# usb_to_can.net
KiCad netlist of a schematic drawn in EAGLE
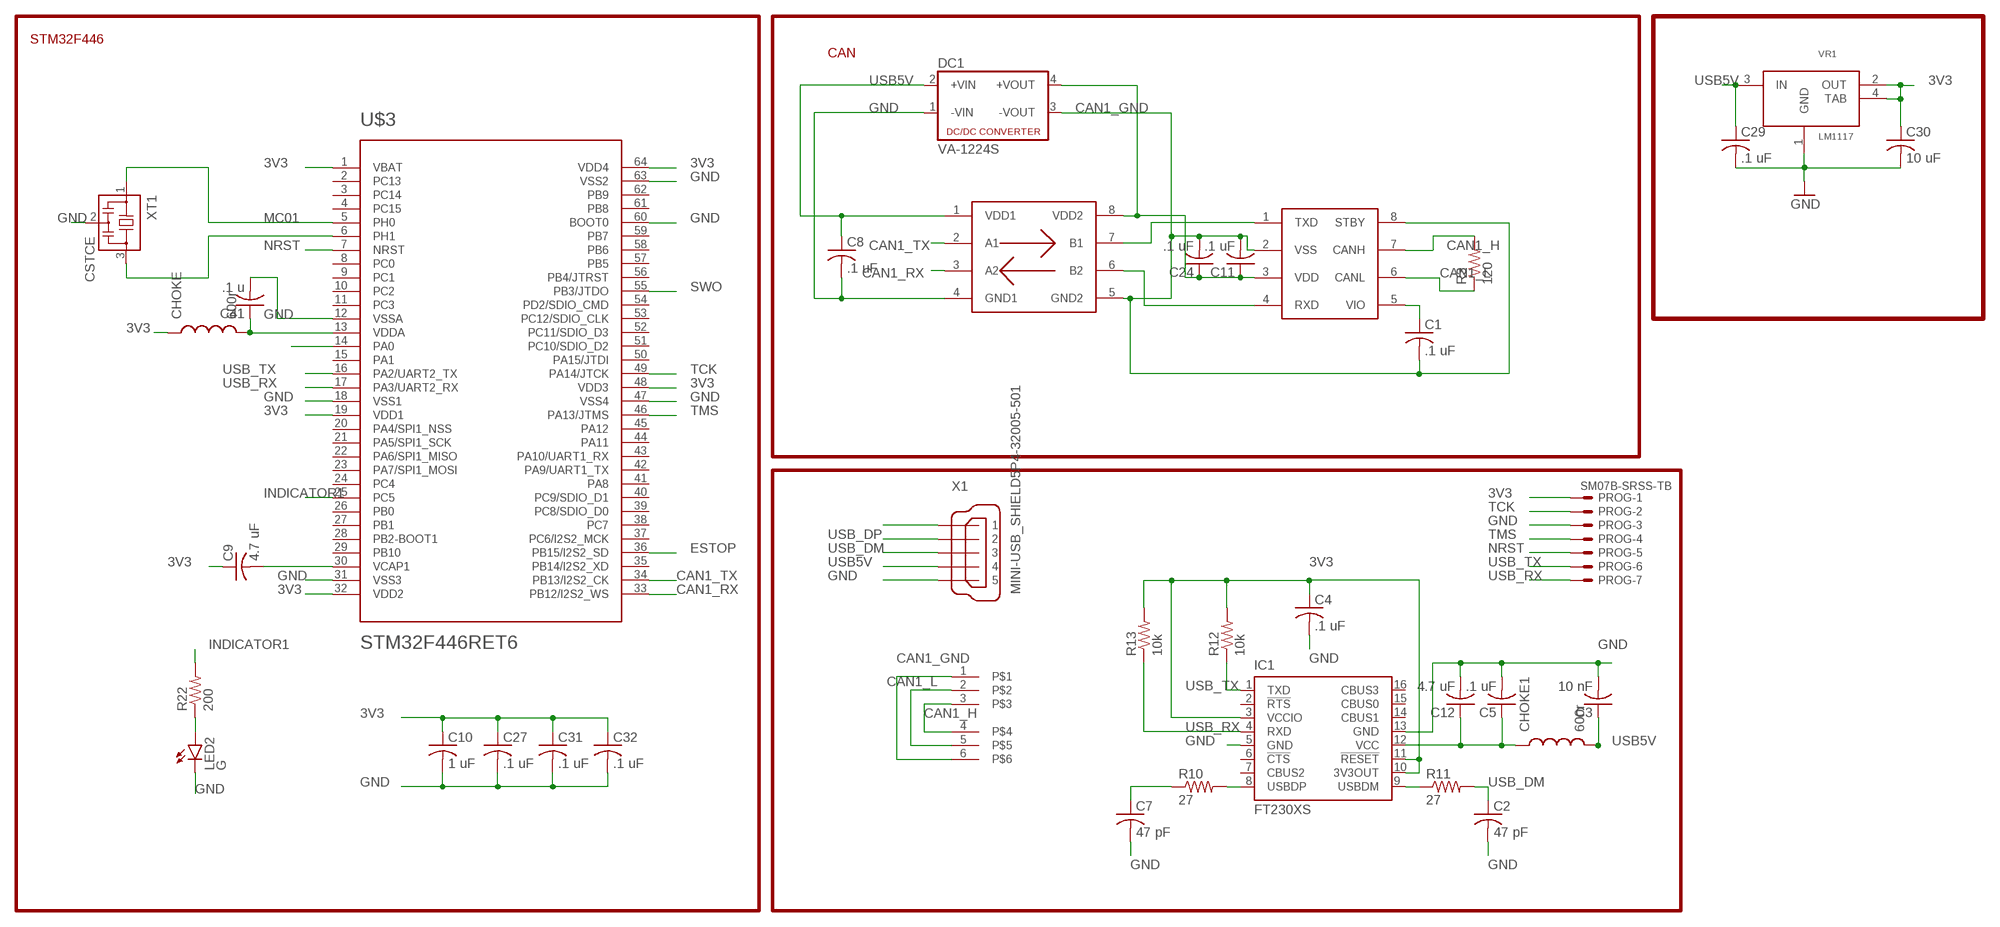
[diagram p0: schematic, sheet 1]

(export (version "E")
  (design (tool "Eeschema 10.0.6"))
  (components
    (comp (ref "C1")
      (value ".1 uF")
      (footprint "eagle-import:C0402K")
      (libsource (lib "eagle-import") (part "C-USC0402K"))
    )
    (comp (ref "C2")
      (value "47 pF")
      (footprint "eagle-import:C0402K")
      (libsource (lib "eagle-import") (part "C-USC0402K"))
    )
    (comp (ref "C3")
      (value "10 nF")
      (footprint "eagle-import:C0402K")
      (libsource (lib "eagle-import") (part "C-USC0402K"))
    )
    (comp (ref "C4")
      (value ".1 uF")
      (footprint "eagle-import:C0402K")
      (libsource (lib "eagle-import") (part "C-USC0402K"))
    )
    (comp (ref "C5")
      (value ".1 uF")
      (footprint "eagle-import:C0402K")
      (libsource (lib "eagle-import") (part "C-USC0402K"))
    )
    (comp (ref "C7")
      (value "47 pF")
      (footprint "eagle-import:C0402K")
      (libsource (lib "eagle-import") (part "C-USC0402K"))
    )
    (comp (ref "C8")
      (value ".1 uF")
      (footprint "eagle-import:C0402K")
      (libsource (lib "eagle-import") (part "C-USC0402K"))
    )
    (comp (ref "C9")
      (value "4.7 uF")
      (footprint "eagle-import:C0402K")
      (libsource (lib "eagle-import") (part "C-USC0402K"))
    )
    (comp (ref "C10")
      (value "1 uF")
      (footprint "eagle-import:C0402K")
      (libsource (lib "eagle-import") (part "C-USC0402K"))
    )
    (comp (ref "C11")
      (value ".1 uF")
      (footprint "eagle-import:C0402K")
      (libsource (lib "eagle-import") (part "C-USC0402K"))
    )
    (comp (ref "C12")
      (value "4.7 uF")
      (footprint "eagle-import:C0402K")
      (libsource (lib "eagle-import") (part "C-USC0402K"))
    )
    (comp (ref "C24")
      (value ".1 uF")
      (footprint "eagle-import:C0402K")
      (libsource (lib "eagle-import") (part "C-USC0402K"))
    )
    (comp (ref "C27")
      (value ".1 uF")
      (footprint "eagle-import:C0402K")
      (libsource (lib "eagle-import") (part "C-USC0402K"))
    )
    (comp (ref "C29")
      (value ".1 uF")
      (footprint "eagle-import:C0402K")
      (libsource (lib "eagle-import") (part "C-USC0402K"))
    )
    (comp (ref "C30")
      (value "10 uF")
      (footprint "eagle-import:C0402K")
      (libsource (lib "eagle-import") (part "C-USC0402K"))
    )
    (comp (ref "C31")
      (value ".1 uF")
      (footprint "eagle-import:C0402K")
      (libsource (lib "eagle-import") (part "C-USC0402K"))
    )
    (comp (ref "C32")
      (value ".1 uF")
      (footprint "eagle-import:C0402K")
      (libsource (lib "eagle-import") (part "C-USC0402K"))
    )
    (comp (ref "C41")
      (value ".1 u")
      (footprint "eagle-import:C0402K")
      (libsource (lib "eagle-import") (part "C-USC0402K"))
    )
    (comp (ref "CHOKE")
      (value "600r")
      (footprint "eagle-import:0603")
      (libsource (lib "eagle-import") (part "INDUCTOR0603"))
    )
    (comp (ref "CHOKE1")
      (value "600r")
      (footprint "eagle-import:0603")
      (libsource (lib "eagle-import") (part "INDUCTOR0603"))
    )
    (comp (ref "DC1")
      (value "VA-1224S")
      (footprint "eagle-import:4SIL")
      (libsource (lib "eagle-import") (part "VA-?S1224"))
    )
    (comp (ref "IC1")
      (value "FT230XS")
      (footprint "eagle-import:SSOP16")
      (libsource (lib "eagle-import") (part "FT230XS"))
    )
    (comp (ref "LED2")
      (value "G")
      (footprint "eagle-import:LED-0603")
      (libsource (lib "eagle-import") (part "LED0603"))
    )
    (comp (ref "PROG")
      (value "SM07B-SRSS-TB")
      (footprint "eagle-import:SM07B-SRSS-TB")
      (libsource (lib "eagle-import") (part "?M07B-SRSS-TBS"))
    )
    (comp (ref "R3")
      (value "120")
      (footprint "eagle-import:R0402")
      (libsource (lib "eagle-import") (part "R-US_R0402"))
    )
    (comp (ref "R10")
      (value "27")
      (footprint "eagle-import:R0402")
      (libsource (lib "eagle-import") (part "R-US_R0402"))
    )
    (comp (ref "R11")
      (value "27")
      (footprint "eagle-import:R0402")
      (libsource (lib "eagle-import") (part "R-US_R0402"))
    )
    (comp (ref "R12")
      (value "10k")
      (footprint "eagle-import:R0402")
      (libsource (lib "eagle-import") (part "R-US_R0402"))
    )
    (comp (ref "R13")
      (value "10k")
      (footprint "eagle-import:R0402")
      (libsource (lib "eagle-import") (part "R-US_R0402"))
    )
    (comp (ref "R22")
      (value "200")
      (footprint "eagle-import:R0402")
      (libsource (lib "eagle-import") (part "R-US_R0402"))
    )
    (comp (ref "U$1")
      (value "6-PIN")
      (footprint "eagle-import:M80-5400642")
      (libsource (lib "eagle-import") (part "6-PIN"))
    )
    (comp (ref "U$3")
      (value "STM32F446RET6")
      (footprint "eagle-import:TQFP64")
      (libsource (lib "eagle-import") (part "STM32F446RET6"))
    )
    (comp (ref "U$4")
      (value "MCP2561")
      (footprint "eagle-import:SO08")
      (libsource (lib "eagle-import") (part "MCP2561"))
    )
    (comp (ref "U$8")
      (value "SI8410")
      (footprint "eagle-import:SO08")
      (libsource (lib "eagle-import") (part "SI8410"))
    )
    (comp (ref "VR1")
      (value "LM1117")
      (footprint "eagle-import:SOT-223")
      (libsource (lib "eagle-import") (part "LM1117"))
    )
    (comp (ref "X1")
      (value "MINI-USB_SHIELD5P4-32005-501")
      (footprint "eagle-import:32005-501")
      (libsource (lib "eagle-import") (part "MINI-USB_SHIELD5P4-32005-501"))
    )
    (comp (ref "XT1")
      (value "CSTCE")
      (footprint "eagle-import:CSTCE")
      (libsource (lib "eagle-import") (part "CSTCE"))
    )
  )
  (nets
    (net (code "1") (name "/3V3") (class "Default")
      (node (ref "C10") (pin "1") (pinfunction "1_1") (pintype "passive"))
      (node (ref "C27") (pin "1") (pinfunction "1_1") (pintype "passive"))
      (node (ref "C30") (pin "1") (pinfunction "1_1") (pintype "passive"))
      (node (ref "C31") (pin "1") (pinfunction "1_1") (pintype "passive"))
      (node (ref "C32") (pin "1") (pinfunction "1_1") (pintype "passive"))
      (node (ref "C4") (pin "1") (pinfunction "1_1") (pintype "passive"))
      (node (ref "C9") (pin "1") (pinfunction "1_1") (pintype "passive"))
      (node (ref "CHOKE") (pin "1") (pinfunction "1_1") (pintype "passive"))
      (node (ref "IC1") (pin "10") (pinfunction "3V3OUT_10") (pintype "output"))
      (node (ref "IC1") (pin "11") (pinfunction "~{RESET}_11") (pintype "input"))
      (node (ref "IC1") (pin "3") (pinfunction "VCCIO_3") (pintype "power_in"))
      (node (ref "PROG") (pin "1") (pinfunction "S_1") (pintype "passive"))
      (node (ref "R12") (pin "2") (pinfunction "2_2") (pintype "passive"))
      (node (ref "R13") (pin "2") (pinfunction "2_2") (pintype "passive"))
      (node (ref "U$3") (pin "1") (pinfunction "VBAT_1") (pintype "bidirectional"))
      (node (ref "U$3") (pin "19") (pinfunction "VDD1_19") (pintype "bidirectional"))
      (node (ref "U$3") (pin "32") (pinfunction "VDD2_32") (pintype "bidirectional"))
      (node (ref "U$3") (pin "48") (pinfunction "VDD3_48") (pintype "bidirectional"))
      (node (ref "U$3") (pin "64") (pinfunction "VDD4_64") (pintype "bidirectional"))
      (node (ref "VR1") (pin "2") (pinfunction "OUT_2") (pintype "bidirectional"))
      (node (ref "VR1") (pin "4") (pinfunction "TAB_4") (pintype "bidirectional"))
    )
    (net (code "2") (name "/CAN1_GND") (class "Default")
      (node (ref "C1") (pin "2") (pinfunction "2_2") (pintype "passive"))
      (node (ref "C11") (pin "2") (pinfunction "2_2") (pintype "passive"))
      (node (ref "C24") (pin "2") (pinfunction "2_2") (pintype "passive"))
      (node (ref "DC1") (pin "3") (pinfunction "-VOUT_3") (pintype "passive"))
      (node (ref "U$1") (pin "1") (pinfunction "P$1_1") (pintype "bidirectional"))
      (node (ref "U$1") (pin "6") (pinfunction "P$6_6") (pintype "bidirectional"))
      (node (ref "U$4") (pin "2") (pinfunction "VSS_2") (pintype "bidirectional"))
      (node (ref "U$4") (pin "8") (pinfunction "STBY_8") (pintype "bidirectional"))
      (node (ref "U$8") (pin "5") (pinfunction "GND2_5") (pintype "bidirectional"))
    )
    (net (code "3") (name "/CAN1_H") (class "Default")
      (node (ref "R3") (pin "2") (pinfunction "2_2") (pintype "passive"))
      (node (ref "U$1") (pin "3") (pinfunction "P$3_3") (pintype "bidirectional"))
      (node (ref "U$1") (pin "4") (pinfunction "P$4_4") (pintype "bidirectional"))
      (node (ref "U$4") (pin "7") (pinfunction "CANH_7") (pintype "bidirectional"))
    )
    (net (code "4") (name "/CAN1_L") (class "Default")
      (node (ref "R3") (pin "1") (pinfunction "1_1") (pintype "passive"))
      (node (ref "U$1") (pin "2") (pinfunction "P$2_2") (pintype "bidirectional"))
      (node (ref "U$1") (pin "5") (pinfunction "P$5_5") (pintype "bidirectional"))
      (node (ref "U$4") (pin "6") (pinfunction "CANL_6") (pintype "bidirectional"))
    )
    (net (code "5") (name "/CAN1_RX") (class "Default")
      (node (ref "U$3") (pin "33") (pinfunction "PB12/I2S2_WS_33") (pintype "bidirectional"))
      (node (ref "U$8") (pin "3") (pinfunction "A2_3") (pintype "bidirectional"))
    )
    (net (code "6") (name "/CAN1_TX") (class "Default")
      (node (ref "U$3") (pin "34") (pinfunction "PB13/I2S2_CK_34") (pintype "bidirectional"))
      (node (ref "U$8") (pin "2") (pinfunction "A1_2") (pintype "bidirectional"))
    )
    (net (code "7") (name "/ESTOP") (class "Default")
      (node (ref "U$3") (pin "36") (pinfunction "PB15/I2S2_SD_36") (pintype "bidirectional"))
    )
    (net (code "8") (name "/INDICATOR1") (class "Default")
      (node (ref "R22") (pin "2") (pinfunction "2_2") (pintype "passive"))
      (node (ref "U$3") (pin "25") (pinfunction "PC5_25") (pintype "bidirectional"))
    )
    (net (code "9") (name "/MC01") (class "Default")
      (node (ref "U$3") (pin "5") (pinfunction "PH0_5") (pintype "bidirectional"))
      (node (ref "XT1") (pin "1") (pinfunction "1_1") (pintype "passive"))
    )
    (net (code "10") (name "/NRST") (class "Default")
      (node (ref "PROG") (pin "5") (pinfunction "S_5") (pintype "passive"))
      (node (ref "U$3") (pin "7") (pinfunction "NRST_7") (pintype "bidirectional"))
    )
    (net (code "11") (name "/SWO") (class "Default")
      (node (ref "U$3") (pin "55") (pinfunction "PB3/JTDO_55") (pintype "bidirectional"))
    )
    (net (code "12") (name "/TCK") (class "Default")
      (node (ref "PROG") (pin "2") (pinfunction "S_2") (pintype "passive"))
      (node (ref "U$3") (pin "49") (pinfunction "PA14/JTCK_49") (pintype "bidirectional"))
    )
    (net (code "13") (name "/TMS") (class "Default")
      (node (ref "PROG") (pin "4") (pinfunction "S_4") (pintype "passive"))
      (node (ref "U$3") (pin "46") (pinfunction "PA13/JTMS_46") (pintype "bidirectional"))
    )
    (net (code "14") (name "/USB5V") (class "Default")
      (node (ref "C29") (pin "1") (pinfunction "1_1") (pintype "passive"))
      (node (ref "C3") (pin "1") (pinfunction "1_1") (pintype "passive"))
      (node (ref "C8") (pin "1") (pinfunction "1_1") (pintype "passive"))
      (node (ref "CHOKE1") (pin "2") (pinfunction "2_2") (pintype "passive"))
      (node (ref "DC1") (pin "2") (pinfunction "+VIN_2") (pintype "passive"))
      (node (ref "U$8") (pin "1") (pinfunction "VDD1_1") (pintype "bidirectional"))
      (node (ref "VR1") (pin "3") (pinfunction "IN_3") (pintype "bidirectional"))
      (node (ref "X1") (pin "4") (pinfunction "4_4") (pintype "passive"))
    )
    (net (code "15") (name "/USB_DM") (class "Default")
      (node (ref "C2") (pin "1") (pinfunction "1_1") (pintype "passive"))
      (node (ref "R11") (pin "2") (pinfunction "2_2") (pintype "passive"))
      (node (ref "X1") (pin "3") (pinfunction "3_3") (pintype "passive"))
    )
    (net (code "16") (name "/USB_DP") (class "Default")
      (node (ref "C7") (pin "1") (pinfunction "1_1") (pintype "passive"))
      (node (ref "R10") (pin "1") (pinfunction "1_1") (pintype "passive"))
      (node (ref "X1") (pin "2") (pinfunction "2_2") (pintype "passive"))
    )
    (net (code "17") (name "/USB_RX") (class "Default")
      (node (ref "IC1") (pin "4") (pinfunction "RXD_4") (pintype "input"))
      (node (ref "PROG") (pin "7") (pinfunction "S_7") (pintype "passive"))
      (node (ref "R13") (pin "1") (pinfunction "1_1") (pintype "passive"))
      (node (ref "U$3") (pin "17") (pinfunction "PA3/UART2_RX_17") (pintype "bidirectional"))
    )
    (net (code "18") (name "/USB_TX") (class "Default")
      (node (ref "IC1") (pin "1") (pinfunction "TXD_1") (pintype "output"))
      (node (ref "PROG") (pin "6") (pinfunction "S_6") (pintype "passive"))
      (node (ref "R12") (pin "1") (pinfunction "1_1") (pintype "passive"))
      (node (ref "U$3") (pin "16") (pinfunction "PA2/UART2_TX_16") (pintype "bidirectional"))
    )
    (net (code "19") (name "GND") (class "Default")
      (node (ref "C10") (pin "2") (pinfunction "2_2") (pintype "passive"))
      (node (ref "C12") (pin "2") (pinfunction "2_2") (pintype "passive"))
      (node (ref "C2") (pin "2") (pinfunction "2_2") (pintype "passive"))
      (node (ref "C27") (pin "2") (pinfunction "2_2") (pintype "passive"))
      (node (ref "C29") (pin "2") (pinfunction "2_2") (pintype "passive"))
      (node (ref "C3") (pin "2") (pinfunction "2_2") (pintype "passive"))
      (node (ref "C30") (pin "2") (pinfunction "2_2") (pintype "passive"))
      (node (ref "C31") (pin "2") (pinfunction "2_2") (pintype "passive"))
      (node (ref "C32") (pin "2") (pinfunction "2_2") (pintype "passive"))
      (node (ref "C4") (pin "2") (pinfunction "2_2") (pintype "passive"))
      (node (ref "C41") (pin "2") (pinfunction "2_2") (pintype "passive"))
      (node (ref "C5") (pin "2") (pinfunction "2_2") (pintype "passive"))
      (node (ref "C7") (pin "2") (pinfunction "2_2") (pintype "passive"))
      (node (ref "C8") (pin "2") (pinfunction "2_2") (pintype "passive"))
      (node (ref "DC1") (pin "1") (pinfunction "-VIN_1") (pintype "passive"))
      (node (ref "IC1") (pin "13") (pinfunction "GND_13") (pintype "power_in"))
      (node (ref "IC1") (pin "5") (pinfunction "GND_5") (pintype "power_in"))
      (node (ref "LED2") (pin "C") (pinfunction "C_C") (pintype "passive"))
      (node (ref "PROG") (pin "3") (pinfunction "S_3") (pintype "passive"))
      (node (ref "U$3") (pin "12") (pinfunction "VSSA_12") (pintype "bidirectional"))
      (node (ref "U$3") (pin "18") (pinfunction "VSS1_18") (pintype "bidirectional"))
      (node (ref "U$3") (pin "31") (pinfunction "VSS3_31") (pintype "bidirectional"))
      (node (ref "U$3") (pin "47") (pinfunction "VSS4_47") (pintype "bidirectional"))
      (node (ref "U$3") (pin "60") (pinfunction "BOOT0_60") (pintype "bidirectional"))
      (node (ref "U$3") (pin "63") (pinfunction "VSS2_63") (pintype "bidirectional"))
      (node (ref "U$8") (pin "4") (pinfunction "GND1_4") (pintype "bidirectional"))
      (node (ref "VR1") (pin "1") (pinfunction "GND_1") (pintype "bidirectional"))
      (node (ref "X1") (pin "5") (pinfunction "5_5") (pintype "passive"))
      (node (ref "XT1") (pin "2") (pinfunction "2_2") (pintype "passive"))
    )
    (net (code "20") (name "Net-(DC1-+VOUT)") (class "Default")
      (node (ref "C11") (pin "1") (pinfunction "1_1") (pintype "passive"))
      (node (ref "C24") (pin "1") (pinfunction "1_1") (pintype "passive"))
      (node (ref "DC1") (pin "4") (pinfunction "+VOUT_4") (pintype "passive"))
      (node (ref "U$4") (pin "3") (pinfunction "VDD_3") (pintype "bidirectional"))
      (node (ref "U$8") (pin "8") (pinfunction "VDD2_8") (pintype "bidirectional"))
    )
    (net (code "21") (name "Net-(IC1-USBDM)") (class "Default")
      (node (ref "IC1") (pin "9") (pinfunction "USBDM_9") (pintype "input"))
      (node (ref "R11") (pin "1") (pinfunction "1_1") (pintype "passive"))
    )
    (net (code "22") (name "Net-(IC1-USBDP)") (class "Default")
      (node (ref "IC1") (pin "8") (pinfunction "USBDP_8") (pintype "input"))
      (node (ref "R10") (pin "2") (pinfunction "2_2") (pintype "passive"))
    )
    (net (code "23") (name "Net-(IC1-VCC)") (class "Default")
      (node (ref "C12") (pin "1") (pinfunction "1_1") (pintype "passive"))
      (node (ref "C5") (pin "1") (pinfunction "1_1") (pintype "passive"))
      (node (ref "CHOKE1") (pin "1") (pinfunction "1_1") (pintype "passive"))
      (node (ref "IC1") (pin "12") (pinfunction "VCC_12") (pintype "power_in"))
    )
    (net (code "24") (name "Net-(LED2-PadA)") (class "Default")
      (node (ref "LED2") (pin "A") (pinfunction "A_A") (pintype "passive"))
      (node (ref "R22") (pin "1") (pinfunction "1_1") (pintype "passive"))
    )
    (net (code "25") (name "Net-(U$3-PH1)") (class "Default")
      (node (ref "U$3") (pin "6") (pinfunction "PH1_6") (pintype "bidirectional"))
      (node (ref "XT1") (pin "3") (pinfunction "3_3") (pintype "passive"))
    )
    (net (code "26") (name "Net-(U$3-VCAP1)") (class "Default")
      (node (ref "C9") (pin "2") (pinfunction "2_2") (pintype "passive"))
      (node (ref "U$3") (pin "30") (pinfunction "VCAP1_30") (pintype "bidirectional"))
    )
    (net (code "27") (name "Net-(U$3-VDDA)") (class "Default")
      (node (ref "C41") (pin "1") (pinfunction "1_1") (pintype "passive"))
      (node (ref "CHOKE") (pin "2") (pinfunction "2_2") (pintype "passive"))
      (node (ref "U$3") (pin "13") (pinfunction "VDDA_13") (pintype "bidirectional"))
    )
    (net (code "28") (name "Net-(U$4-RXD)") (class "Default")
      (node (ref "U$4") (pin "4") (pinfunction "RXD_4") (pintype "bidirectional"))
      (node (ref "U$8") (pin "6") (pinfunction "B2_6") (pintype "bidirectional"))
    )
    (net (code "29") (name "Net-(U$4-TXD)") (class "Default")
      (node (ref "U$4") (pin "1") (pinfunction "TXD_1") (pintype "bidirectional"))
      (node (ref "U$8") (pin "7") (pinfunction "B1_7") (pintype "bidirectional"))
    )
    (net (code "30") (name "Net-(U$4-VIO)") (class "Default")
      (node (ref "C1") (pin "1") (pinfunction "1_1") (pintype "passive"))
      (node (ref "U$4") (pin "5") (pinfunction "VIO_5") (pintype "bidirectional"))
    )
    (net (code "31") (name "unconnected-(IC1-CBUS0-Pad15)") (class "Default")
      (node (ref "IC1") (pin "15") (pinfunction "CBUS0_15") (pintype "bidirectional"))
    )
    (net (code "32") (name "unconnected-(IC1-CBUS1-Pad14)") (class "Default")
      (node (ref "IC1") (pin "14") (pinfunction "CBUS1_14") (pintype "bidirectional"))
    )
    (net (code "33") (name "unconnected-(IC1-CBUS2-Pad7)") (class "Default")
      (node (ref "IC1") (pin "7") (pinfunction "CBUS2_7") (pintype "bidirectional"))
    )
    (net (code "34") (name "unconnected-(IC1-CBUS3-Pad16)") (class "Default")
      (node (ref "IC1") (pin "16") (pinfunction "CBUS3_16") (pintype "bidirectional"))
    )
    (net (code "35") (name "unconnected-(IC1-~{CTS}-Pad6)") (class "Default")
      (node (ref "IC1") (pin "6") (pinfunction "~{CTS}_6") (pintype "input"))
    )
    (net (code "36") (name "unconnected-(IC1-~{RTS}-Pad2)") (class "Default")
      (node (ref "IC1") (pin "2") (pinfunction "~{RTS}_2") (pintype "output"))
    )
    (net (code "37") (name "unconnected-(U$3-PA0-Pad14)") (class "Default")
      (node (ref "U$3") (pin "14") (pinfunction "PA0_14") (pintype "bidirectional"))
    )
    (net (code "38") (name "unconnected-(U$3-PA1-Pad15)") (class "Default")
      (node (ref "U$3") (pin "15") (pinfunction "PA1_15") (pintype "bidirectional"))
    )
    (net (code "39") (name "unconnected-(U$3-PA4{slash}SPI1_NSS-Pad20)") (class "Default")
      (node (ref "U$3") (pin "20") (pinfunction "PA4/SPI1_NSS_20") (pintype "bidirectional"))
    )
    (net (code "40") (name "unconnected-(U$3-PA5{slash}SPI1_SCK-Pad21)") (class "Default")
      (node (ref "U$3") (pin "21") (pinfunction "PA5/SPI1_SCK_21") (pintype "bidirectional"))
    )
    (net (code "41") (name "unconnected-(U$3-PA6{slash}SPI1_MISO-Pad22)") (class "Default")
      (node (ref "U$3") (pin "22") (pinfunction "PA6/SPI1_MISO_22") (pintype "bidirectional"))
    )
    (net (code "42") (name "unconnected-(U$3-PA7{slash}SPI1_MOSI-Pad23)") (class "Default")
      (node (ref "U$3") (pin "23") (pinfunction "PA7/SPI1_MOSI_23") (pintype "bidirectional"))
    )
    (net (code "43") (name "unconnected-(U$3-PA8-Pad41)") (class "Default")
      (node (ref "U$3") (pin "41") (pinfunction "PA8_41") (pintype "bidirectional"))
    )
    (net (code "44") (name "unconnected-(U$3-PA9{slash}UART1_TX-Pad42)") (class "Default")
      (node (ref "U$3") (pin "42") (pinfunction "PA9/UART1_TX_42") (pintype "bidirectional"))
    )
    (net (code "45") (name "unconnected-(U$3-PA10{slash}UART1_RX-Pad43)") (class "Default")
      (node (ref "U$3") (pin "43") (pinfunction "PA10/UART1_RX_43") (pintype "bidirectional"))
    )
    (net (code "46") (name "unconnected-(U$3-PA11-Pad44)") (class "Default")
      (node (ref "U$3") (pin "44") (pinfunction "PA11_44") (pintype "bidirectional"))
    )
    (net (code "47") (name "unconnected-(U$3-PA12-Pad45)") (class "Default")
      (node (ref "U$3") (pin "45") (pinfunction "PA12_45") (pintype "bidirectional"))
    )
    (net (code "48") (name "unconnected-(U$3-PA15{slash}JTDI-Pad50)") (class "Default")
      (node (ref "U$3") (pin "50") (pinfunction "PA15/JTDI_50") (pintype "bidirectional"))
    )
    (net (code "49") (name "unconnected-(U$3-PB0-Pad26)") (class "Default")
      (node (ref "U$3") (pin "26") (pinfunction "PB0_26") (pintype "bidirectional"))
    )
    (net (code "50") (name "unconnected-(U$3-PB1-Pad27)") (class "Default")
      (node (ref "U$3") (pin "27") (pinfunction "PB1_27") (pintype "bidirectional"))
    )
    (net (code "51") (name "unconnected-(U$3-PB2-BOOT1-Pad28)") (class "Default")
      (node (ref "U$3") (pin "28") (pinfunction "PB2-BOOT1_28") (pintype "bidirectional"))
    )
    (net (code "52") (name "unconnected-(U$3-PB4{slash}JTRST-Pad56)") (class "Default")
      (node (ref "U$3") (pin "56") (pinfunction "PB4/JTRST_56") (pintype "bidirectional"))
    )
    (net (code "53") (name "unconnected-(U$3-PB5-Pad57)") (class "Default")
      (node (ref "U$3") (pin "57") (pinfunction "PB5_57") (pintype "bidirectional"))
    )
    (net (code "54") (name "unconnected-(U$3-PB6-Pad58)") (class "Default")
      (node (ref "U$3") (pin "58") (pinfunction "PB6_58") (pintype "bidirectional"))
    )
    (net (code "55") (name "unconnected-(U$3-PB7-Pad59)") (class "Default")
      (node (ref "U$3") (pin "59") (pinfunction "PB7_59") (pintype "bidirectional"))
    )
    (net (code "56") (name "unconnected-(U$3-PB8-Pad61)") (class "Default")
      (node (ref "U$3") (pin "61") (pinfunction "PB8_61") (pintype "bidirectional"))
    )
    (net (code "57") (name "unconnected-(U$3-PB9-Pad62)") (class "Default")
      (node (ref "U$3") (pin "62") (pinfunction "PB9_62") (pintype "bidirectional"))
    )
    (net (code "58") (name "unconnected-(U$3-PB10-Pad29)") (class "Default")
      (node (ref "U$3") (pin "29") (pinfunction "PB10_29") (pintype "bidirectional"))
    )
    (net (code "59") (name "unconnected-(U$3-PB14{slash}I2S2_XD-Pad35)") (class "Default")
      (node (ref "U$3") (pin "35") (pinfunction "PB14/I2S2_XD_35") (pintype "bidirectional"))
    )
    (net (code "60") (name "unconnected-(U$3-PC0-Pad8)") (class "Default")
      (node (ref "U$3") (pin "8") (pinfunction "PC0_8") (pintype "bidirectional"))
    )
    (net (code "61") (name "unconnected-(U$3-PC1-Pad9)") (class "Default")
      (node (ref "U$3") (pin "9") (pinfunction "PC1_9") (pintype "bidirectional"))
    )
    (net (code "62") (name "unconnected-(U$3-PC2-Pad10)") (class "Default")
      (node (ref "U$3") (pin "10") (pinfunction "PC2_10") (pintype "bidirectional"))
    )
    (net (code "63") (name "unconnected-(U$3-PC3-Pad11)") (class "Default")
      (node (ref "U$3") (pin "11") (pinfunction "PC3_11") (pintype "bidirectional"))
    )
    (net (code "64") (name "unconnected-(U$3-PC4-Pad24)") (class "Default")
      (node (ref "U$3") (pin "24") (pinfunction "PC4_24") (pintype "bidirectional"))
    )
    (net (code "65") (name "unconnected-(U$3-PC6{slash}I2S2_MCK-Pad37)") (class "Default")
      (node (ref "U$3") (pin "37") (pinfunction "PC6/I2S2_MCK_37") (pintype "bidirectional"))
    )
    (net (code "66") (name "unconnected-(U$3-PC7-Pad38)") (class "Default")
      (node (ref "U$3") (pin "38") (pinfunction "PC7_38") (pintype "bidirectional"))
    )
    (net (code "67") (name "unconnected-(U$3-PC8{slash}SDIO_D0-Pad39)") (class "Default")
      (node (ref "U$3") (pin "39") (pinfunction "PC8/SDIO_D0_39") (pintype "bidirectional"))
    )
    (net (code "68") (name "unconnected-(U$3-PC9{slash}SDIO_D1-Pad40)") (class "Default")
      (node (ref "U$3") (pin "40") (pinfunction "PC9/SDIO_D1_40") (pintype "bidirectional"))
    )
    (net (code "69") (name "unconnected-(U$3-PC10{slash}SDIO_D2-Pad51)") (class "Default")
      (node (ref "U$3") (pin "51") (pinfunction "PC10/SDIO_D2_51") (pintype "bidirectional"))
    )
    (net (code "70") (name "unconnected-(U$3-PC11{slash}SDIO_D3-Pad52)") (class "Default")
      (node (ref "U$3") (pin "52") (pinfunction "PC11/SDIO_D3_52") (pintype "bidirectional"))
    )
    (net (code "71") (name "unconnected-(U$3-PC12{slash}SDIO_CLK-Pad53)") (class "Default")
      (node (ref "U$3") (pin "53") (pinfunction "PC12/SDIO_CLK_53") (pintype "bidirectional"))
    )
    (net (code "72") (name "unconnected-(U$3-PC13-Pad2)") (class "Default")
      (node (ref "U$3") (pin "2") (pinfunction "PC13_2") (pintype "bidirectional"))
    )
    (net (code "73") (name "unconnected-(U$3-PC14-Pad3)") (class "Default")
      (node (ref "U$3") (pin "3") (pinfunction "PC14_3") (pintype "bidirectional"))
    )
    (net (code "74") (name "unconnected-(U$3-PC15-Pad4)") (class "Default")
      (node (ref "U$3") (pin "4") (pinfunction "PC15_4") (pintype "bidirectional"))
    )
    (net (code "75") (name "unconnected-(U$3-PD2{slash}SDIO_CMD-Pad54)") (class "Default")
      (node (ref "U$3") (pin "54") (pinfunction "PD2/SDIO_CMD_54") (pintype "bidirectional"))
    )
    (net (code "76") (name "unconnected-(X1-Pad1)") (class "Default")
      (node (ref "X1") (pin "1") (pinfunction "1_1") (pintype "passive"))
    )
  )
)
